# f_divider.net
KiCad netlist of a schematic drawn in EAGLE
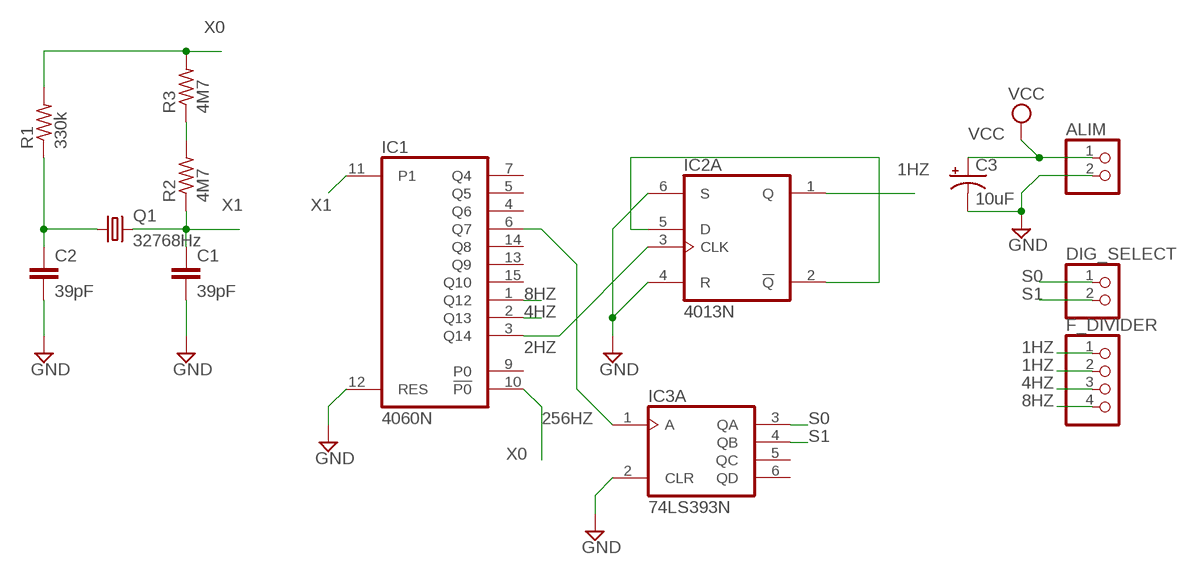
[diagram p0: schematic, sheet 1]

(export (version "E")
  (design (tool "Eeschema 10.0.6"))
  (components
    (comp (ref "ALIM")
      (value "PINHD-1X2")
      (footprint "eagle-import:1X02")
      (libsource (lib "eagle-import") (part "PINHD-1X2"))
    )
    (comp (ref "C1")
      (value "39pF")
      (footprint "eagle-import:CAP-PTH-SMALL-KIT")
      (libsource (lib "eagle-import") (part "0.1UF-50V-20%(PTH)KIT-EZ"))
    )
    (comp (ref "C2")
      (value "39pF")
      (footprint "eagle-import:CAP-PTH-SMALL-KIT")
      (libsource (lib "eagle-import") (part "0.1UF-50V-20%(PTH)KIT-EZ"))
    )
    (comp (ref "C3")
      (value "10uF")
      (footprint "eagle-import:CPOL-RADIAL-10UF-25V")
      (libsource (lib "eagle-import") (part "10UF-25V-20%(PTH)"))
    )
    (comp (ref "DIG_SELECT")
      (value "PINHD-1X2")
      (footprint "eagle-import:1X02")
      (libsource (lib "eagle-import") (part "PINHD-1X2"))
    )
    (comp (ref "F_DIVIDER")
      (value "PINHD-1X4")
      (footprint "eagle-import:1X04")
      (libsource (lib "eagle-import") (part "PINHD-1X4"))
    )
    (comp (ref "IC1")
      (value "4060N")
      (footprint "eagle-import:DIL16")
      (libsource (lib "eagle-import") (part "4060N"))
    )
    (comp (ref "IC2")
      (value "4013N")
      (footprint "eagle-import:DIL14")
      (libsource (lib "eagle-import") (part "4013N"))
    )
    (comp (ref "IC3")
      (value "74LS393N")
      (footprint "eagle-import:DIL14")
      (libsource (lib "eagle-import") (part "74393NLS"))
    )
    (comp (ref "Q1")
      (value "32768Hz")
      (footprint "eagle-import:TC26H")
      (libsource (lib "eagle-import") (part "CRYSTALTC26H"))
    )
    (comp (ref "R1")
      (value "330k")
      (footprint "eagle-import:0204_7")
      (libsource (lib "eagle-import") (part "R-US_0204/7"))
    )
    (comp (ref "R2")
      (value "4M7")
      (footprint "eagle-import:0204_7")
      (libsource (lib "eagle-import") (part "R-US_0204/7"))
    )
    (comp (ref "R3")
      (value "4M7")
      (footprint "eagle-import:0204_7")
      (libsource (lib "eagle-import") (part "R-US_0204/7"))
    )
  )
  (nets
    (net (code "1") (name "/1HZ") (class "Default")
      (node (ref "F_DIVIDER") (pin "1") (pinfunction "1_1") (pintype "passive"))
      (node (ref "F_DIVIDER") (pin "2") (pinfunction "2_2") (pintype "passive"))
      (node (ref "IC2") (pin "1") (pinfunction "Q_1") (pintype "output"))
    )
    (net (code "2") (name "/2HZ") (class "Default")
      (node (ref "IC1") (pin "3") (pinfunction "Q14_3") (pintype "output"))
      (node (ref "IC2") (pin "3") (pinfunction "CLK_3") (pintype "input"))
    )
    (net (code "3") (name "/4HZ") (class "Default")
      (node (ref "F_DIVIDER") (pin "3") (pinfunction "3_3") (pintype "passive"))
      (node (ref "IC1") (pin "2") (pinfunction "Q13_2") (pintype "output"))
    )
    (net (code "4") (name "/8HZ") (class "Default")
      (node (ref "F_DIVIDER") (pin "4") (pinfunction "4_4") (pintype "passive"))
      (node (ref "IC1") (pin "1") (pinfunction "Q12_1") (pintype "output"))
    )
    (net (code "5") (name "/256HZ") (class "Default")
      (node (ref "IC1") (pin "6") (pinfunction "Q7_6") (pintype "output"))
      (node (ref "IC3") (pin "1") (pinfunction "A_1") (pintype "input"))
    )
    (net (code "6") (name "/S0") (class "Default")
      (node (ref "DIG_SELECT") (pin "1") (pinfunction "1_1") (pintype "passive"))
      (node (ref "IC3") (pin "3") (pinfunction "QA_3") (pintype "output"))
    )
    (net (code "7") (name "/S1") (class "Default")
      (node (ref "DIG_SELECT") (pin "2") (pinfunction "2_2") (pintype "passive"))
      (node (ref "IC3") (pin "4") (pinfunction "QB_4") (pintype "output"))
    )
    (net (code "8") (name "/X0") (class "Default")
      (node (ref "IC1") (pin "10") (pinfunction "~{P0}_10") (pintype "output"))
      (node (ref "R1") (pin "2") (pinfunction "2_2") (pintype "passive"))
      (node (ref "R3") (pin "2") (pinfunction "2_2") (pintype "passive"))
    )
    (net (code "9") (name "/X1") (class "Default")
      (node (ref "C1") (pin "1") (pinfunction "1_1") (pintype "passive"))
      (node (ref "IC1") (pin "11") (pinfunction "P1_11") (pintype "input"))
      (node (ref "Q1") (pin "2") (pinfunction "2_2") (pintype "passive"))
      (node (ref "R2") (pin "1") (pinfunction "1_1") (pintype "passive"))
    )
    (net (code "10") (name "GND") (class "Default")
      (node (ref "ALIM") (pin "2") (pinfunction "2_2") (pintype "passive"))
      (node (ref "C1") (pin "2") (pinfunction "2_2") (pintype "passive"))
      (node (ref "C2") (pin "2") (pinfunction "2_2") (pintype "passive"))
      (node (ref "C3") (pin "2") (pinfunction "-_2") (pintype "passive"))
      (node (ref "IC1") (pin "12") (pinfunction "RES_12") (pintype "input"))
      (node (ref "IC2") (pin "4") (pinfunction "R_4") (pintype "input"))
      (node (ref "IC2") (pin "6") (pinfunction "S_6") (pintype "input"))
      (node (ref "IC3") (pin "2") (pinfunction "CLR_2") (pintype "input"))
    )
    (net (code "11") (name "Net-(C2-Pad1)") (class "Default")
      (node (ref "C2") (pin "1") (pinfunction "1_1") (pintype "passive"))
      (node (ref "Q1") (pin "1") (pinfunction "1_1") (pintype "passive"))
      (node (ref "R1") (pin "1") (pinfunction "1_1") (pintype "passive"))
    )
    (net (code "12") (name "Net-(IC2A-D)") (class "Default")
      (node (ref "IC2") (pin "2") (pinfunction "~{Q}_2") (pintype "output"))
      (node (ref "IC2") (pin "5") (pinfunction "D_5") (pintype "input"))
    )
    (net (code "13") (name "Net-(R2-Pad2)") (class "Default")
      (node (ref "R2") (pin "2") (pinfunction "2_2") (pintype "passive"))
      (node (ref "R3") (pin "1") (pinfunction "1_1") (pintype "passive"))
    )
    (net (code "14") (name "VCC") (class "Default")
      (node (ref "ALIM") (pin "1") (pinfunction "1_1") (pintype "passive"))
      (node (ref "C3") (pin "1") (pinfunction "+_1") (pintype "passive"))
    )
    (net (code "15") (name "unconnected-(IC1A-P0-Pad9)") (class "Default")
      (node (ref "IC1") (pin "9") (pinfunction "P0_9") (pintype "output"))
    )
    (net (code "16") (name "unconnected-(IC1A-Q4-Pad7)") (class "Default")
      (node (ref "IC1") (pin "7") (pinfunction "Q4_7") (pintype "output"))
    )
    (net (code "17") (name "unconnected-(IC1A-Q5-Pad5)") (class "Default")
      (node (ref "IC1") (pin "5") (pinfunction "Q5_5") (pintype "output"))
    )
    (net (code "18") (name "unconnected-(IC1A-Q6-Pad4)") (class "Default")
      (node (ref "IC1") (pin "4") (pinfunction "Q6_4") (pintype "output"))
    )
    (net (code "19") (name "unconnected-(IC1A-Q8-Pad14)") (class "Default")
      (node (ref "IC1") (pin "14") (pinfunction "Q8_14") (pintype "output"))
    )
    (net (code "20") (name "unconnected-(IC1A-Q9-Pad13)") (class "Default")
      (node (ref "IC1") (pin "13") (pinfunction "Q9_13") (pintype "output"))
    )
    (net (code "21") (name "unconnected-(IC1A-Q10-Pad15)") (class "Default")
      (node (ref "IC1") (pin "15") (pinfunction "Q10_15") (pintype "output"))
    )
    (net (code "22") (name "unconnected-(IC3A-QC-Pad5)") (class "Default")
      (node (ref "IC3") (pin "5") (pinfunction "QC_5") (pintype "output"))
    )
    (net (code "23") (name "unconnected-(IC3A-QD-Pad6)") (class "Default")
      (node (ref "IC3") (pin "6") (pinfunction "QD_6") (pintype "output"))
    )
  )
)
